# 07_-_Current_Sense.net
KiCad netlist of a schematic drawn in Altium Designer
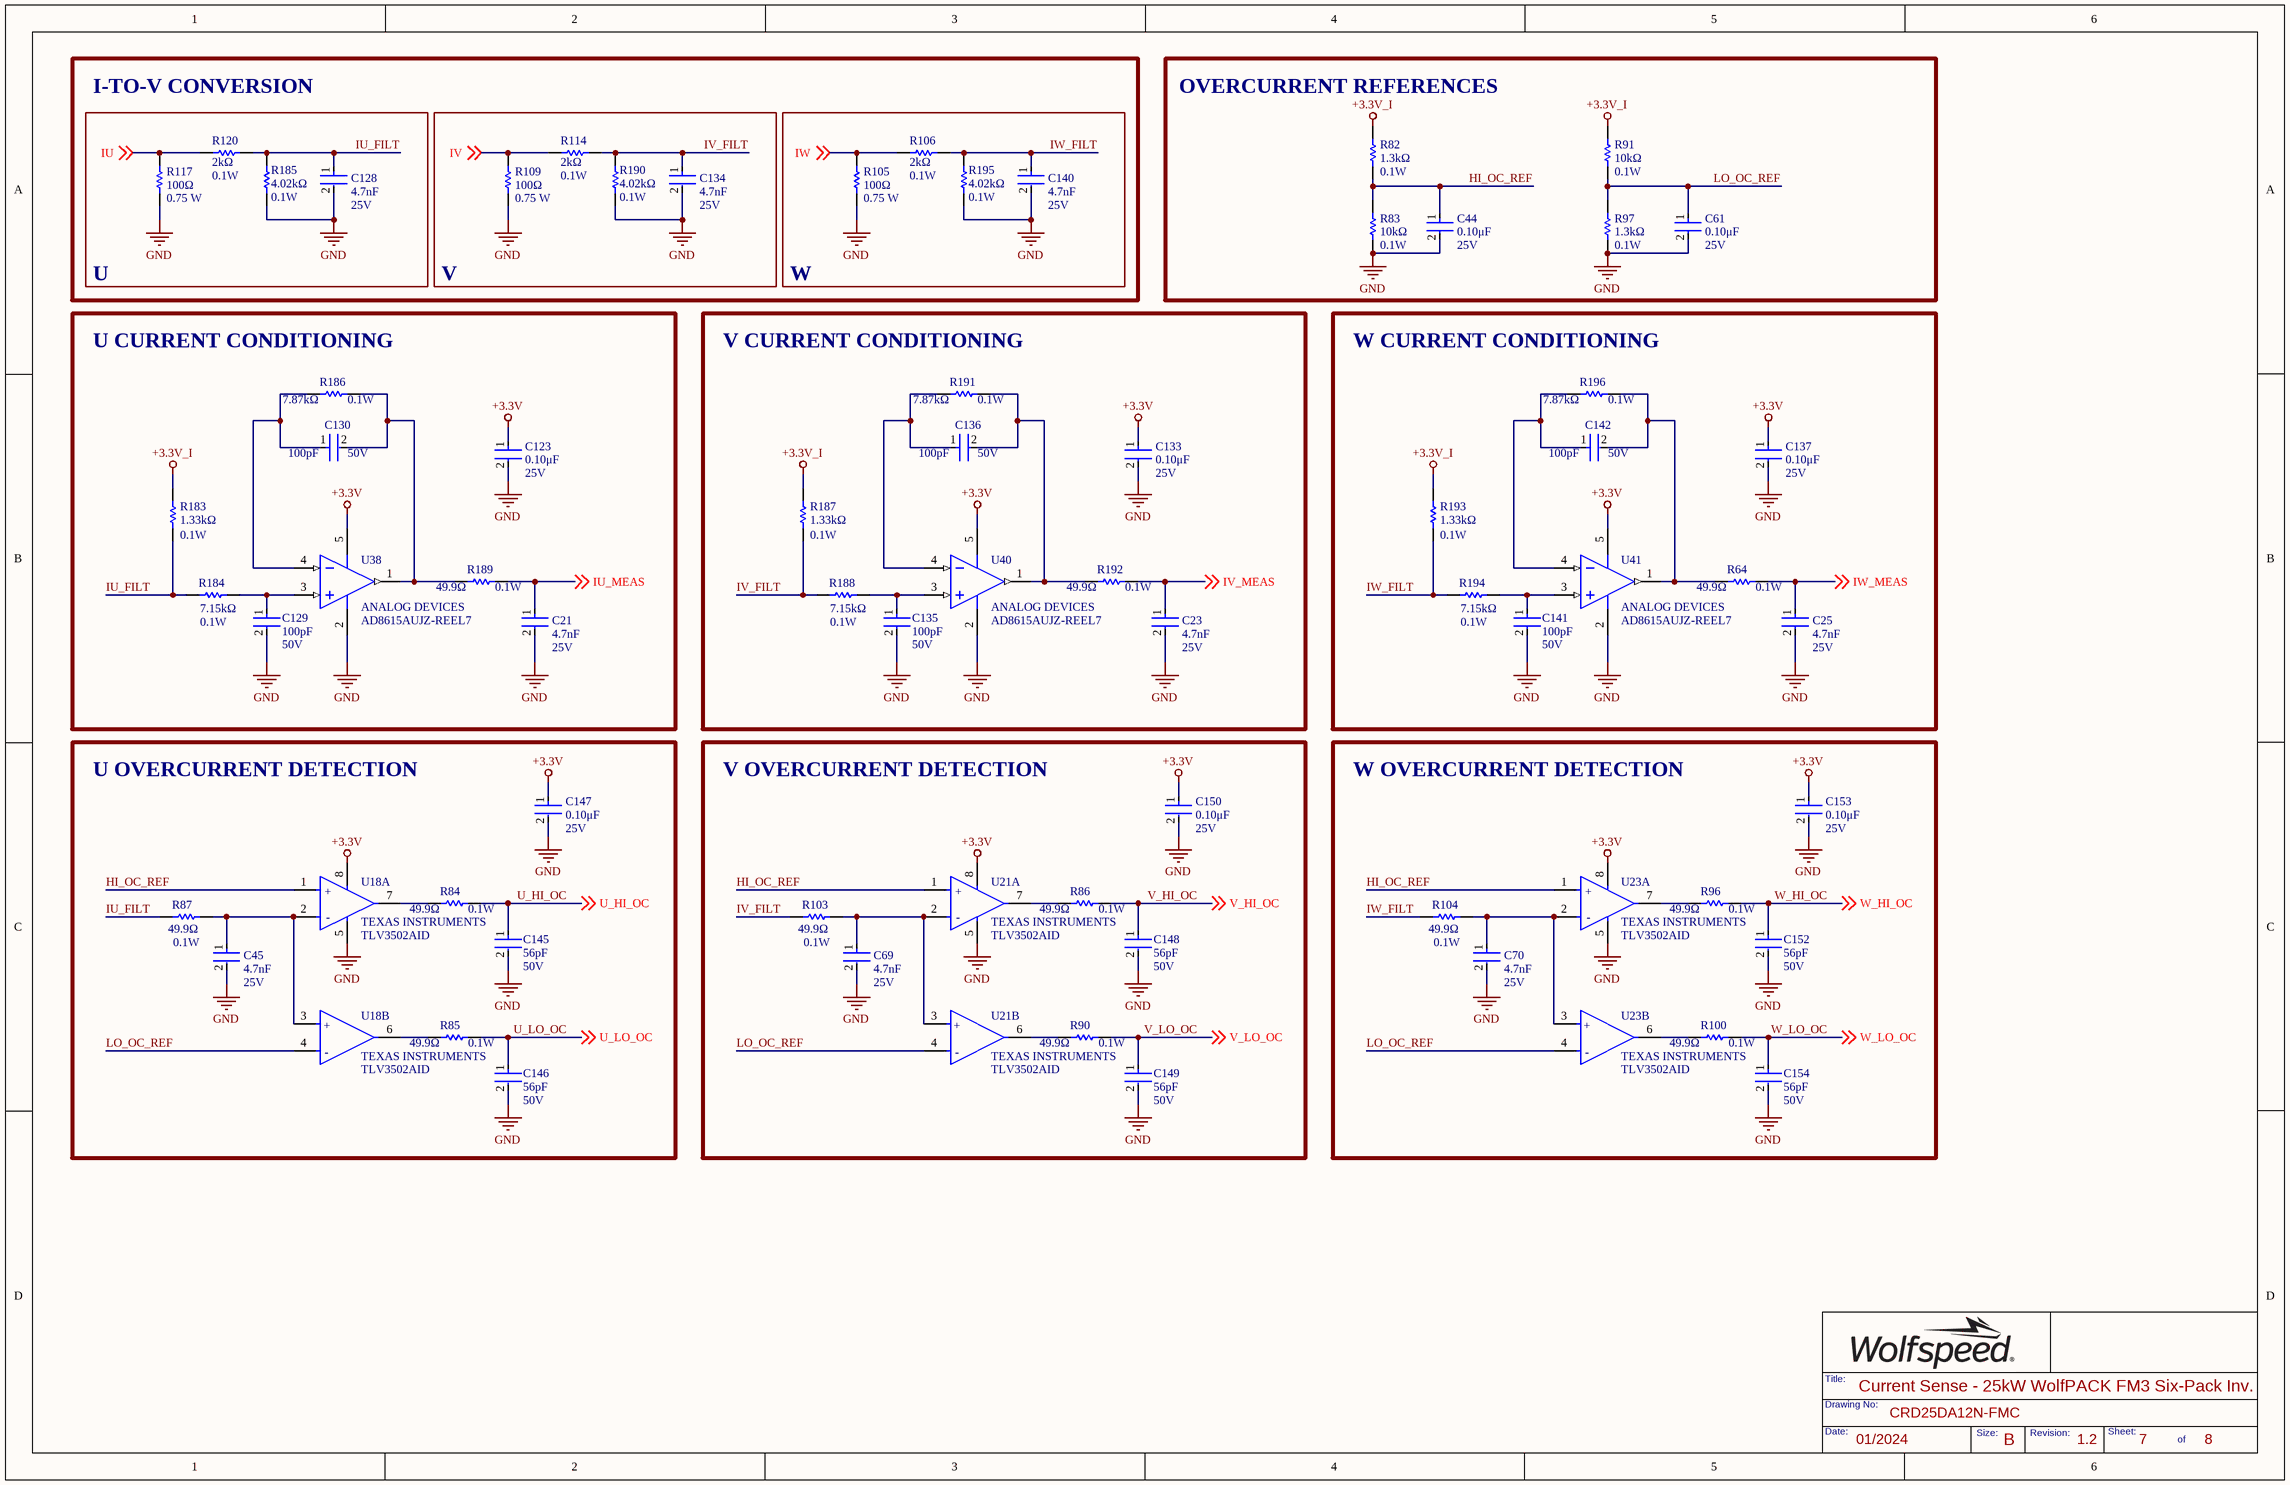
[diagram p0: 07 - Current Sense.SchDoc]

(export (version "E")
  (design (tool "Eeschema 10.0.6"))
  (components
    (comp (ref "C21")
      (value "C0603C472K3RAC7867")
      (footprint "FP-C0603C-CF-IPC_B")
      (description "CAP CER 4700PF 25V 10% X7R 0603")
      (fields
        (field (name "MANUFACTURER") "KEMET")
        (field (name "MANUFACTURER PART NUMBER") "C0603C472K3RACTU")
        (field (name "VOLTAGE RATING") "25V")
        (field (name "CAPACITANCE") "4.7nF")
      )
      (libsource (lib "Inverter_25kW") (part "C0603C472K3RAC7867"))
    )
    (comp (ref "C23")
      (value "C0603C472K3RAC7867")
      (footprint "FP-C0603C-CF-IPC_B")
      (description "CAP CER 4700PF 25V 10% X7R 0603")
      (fields
        (field (name "MANUFACTURER") "KEMET")
        (field (name "MANUFACTURER PART NUMBER") "C0603C472K3RACTU")
        (field (name "VOLTAGE RATING") "25V")
        (field (name "CAPACITANCE") "4.7nF")
      )
      (libsource (lib "Inverter_25kW") (part "C0603C472K3RAC7867"))
    )
    (comp (ref "C25")
      (value "C0603C472K3RAC7867")
      (footprint "FP-C0603C-CF-IPC_B")
      (description "CAP CER 4700PF 25V 10% X7R 0603")
      (fields
        (field (name "MANUFACTURER") "KEMET")
        (field (name "MANUFACTURER PART NUMBER") "C0603C472K3RACTU")
        (field (name "VOLTAGE RATING") "25V")
        (field (name "CAPACITANCE") "4.7nF")
      )
      (libsource (lib "Inverter_25kW") (part "C0603C472K3RAC7867"))
    )
    (comp (ref "C44")
      (value "C0603C104K3RACTU")
      (footprint "FP-C0603C-CF-IPC_B")
      (description "CAP CER 0.1UF 25V X7R 0603")
      (fields
        (field (name "VOLTAGE RATING") "25V")
        (field (name "OCTOPART") "https://octopart.com/c0603c104k3ractu-kemet-127541")
        (field (name "MANUFACTURER") "KEMET")
        (field (name "CAPACITANCE") "0.10μF")
      )
      (libsource (lib "Altium Content Vault") (part "b4654b650e69147ec39a6b967a45e02"))
    )
    (comp (ref "C45")
      (value "C0603C472K3RAC7867")
      (footprint "FP-C0603C-CF-IPC_B")
      (description "CAP CER 4700PF 25V 10% X7R 0603")
      (fields
        (field (name "MANUFACTURER") "KEMET")
        (field (name "MANUFACTURER PART NUMBER") "C0603C472K3RACTU")
        (field (name "VOLTAGE RATING") "25V")
        (field (name "CAPACITANCE") "4.7nF")
      )
      (libsource (lib "Inverter_25kW") (part "C0603C472K3RAC7867"))
    )
    (comp (ref "C61")
      (value "C0603C104K3RACTU")
      (footprint "FP-C0603C-CF-IPC_B")
      (description "CAP CER 0.1UF 25V X7R 0603")
      (fields
        (field (name "VOLTAGE RATING") "25V")
        (field (name "OCTOPART") "https://octopart.com/c0603c104k3ractu-kemet-127541")
        (field (name "MANUFACTURER") "KEMET")
        (field (name "CAPACITANCE") "0.10μF")
      )
      (libsource (lib "Altium Content Vault") (part "b4654b650e69147ec39a6b967a45e02"))
    )
    (comp (ref "C69")
      (value "C0603C472K3RAC7867")
      (footprint "FP-C0603C-CF-IPC_B")
      (description "CAP CER 4700PF 25V 10% X7R 0603")
      (fields
        (field (name "MANUFACTURER") "KEMET")
        (field (name "MANUFACTURER PART NUMBER") "C0603C472K3RACTU")
        (field (name "VOLTAGE RATING") "25V")
        (field (name "CAPACITANCE") "4.7nF")
      )
      (libsource (lib "Inverter_25kW") (part "C0603C472K3RAC7867"))
    )
    (comp (ref "C70")
      (value "C0603C472K3RAC7867")
      (footprint "FP-C0603C-CF-IPC_B")
      (description "CAP CER 4700PF 25V 10% X7R 0603")
      (fields
        (field (name "MANUFACTURER") "KEMET")
        (field (name "MANUFACTURER PART NUMBER") "C0603C472K3RACTU")
        (field (name "VOLTAGE RATING") "25V")
        (field (name "CAPACITANCE") "4.7nF")
      )
      (libsource (lib "Inverter_25kW") (part "C0603C472K3RAC7867"))
    )
    (comp (ref "C123")
      (value "C0603C104K3RACTU")
      (footprint "FP-C0603C-CF-IPC_B")
      (description "CAP CER 0.1UF 25V X7R 0603")
      (fields
        (field (name "VOLTAGE RATING") "25V")
        (field (name "OCTOPART") "https://octopart.com/c0603c104k3ractu-kemet-127541")
        (field (name "MANUFACTURER") "KEMET")
        (field (name "CAPACITANCE") "0.10μF")
      )
      (libsource (lib "Altium Content Vault") (part "b4654b650e69147ec39a6b967a45e02"))
    )
    (comp (ref "C128")
      (value "C0603C472K3RAC7867")
      (footprint "FP-C0603C-CF-IPC_B")
      (description "CAP CER 4700PF 25V 10% X7R 0603")
      (fields
        (field (name "MANUFACTURER") "KEMET")
        (field (name "MANUFACTURER PART NUMBER") "C0603C472K3RACTU")
        (field (name "VOLTAGE RATING") "25V")
        (field (name "CAPACITANCE") "4.7nF")
      )
      (libsource (lib "Inverter_25kW") (part "C0603C472K3RAC7867"))
    )
    (comp (ref "C129")
      (value "CL10C101JB8NNNC")
      (footprint "FP-C0603C-CF-IPC_B")
      (description "CAP CER 100PF 50V C0G/NP0 0603")
      (fields
        (field (name "MANUFACTURER") "SAMSUNG")
        (field (name "TOLERANCE") "5%")
        (field (name "CAPACITANCE") "100pF")
        (field (name "VOLTAGE") "50V")
      )
      (libsource (lib "Inverter_25kW") (part "CL10C101JB8NNNC"))
    )
    (comp (ref "C130")
      (value "CL10C101JB8NNNC")
      (footprint "FP-C0603C-CF-IPC_B")
      (description "CAP CER 100PF 50V C0G/NP0 0603")
      (fields
        (field (name "MANUFACTURER") "SAMSUNG")
        (field (name "TOLERANCE") "5%")
        (field (name "CAPACITANCE") "100pF")
        (field (name "VOLTAGE") "50V")
      )
      (libsource (lib "Inverter_25kW") (part "CL10C101JB8NNNC"))
    )
    (comp (ref "C133")
      (value "C0603C104K3RACTU")
      (footprint "FP-C0603C-CF-IPC_B")
      (description "CAP CER 0.1UF 25V X7R 0603")
      (fields
        (field (name "VOLTAGE RATING") "25V")
        (field (name "OCTOPART") "https://octopart.com/c0603c104k3ractu-kemet-127541")
        (field (name "MANUFACTURER") "KEMET")
        (field (name "CAPACITANCE") "0.10μF")
      )
      (libsource (lib "Altium Content Vault") (part "b4654b650e69147ec39a6b967a45e02"))
    )
    (comp (ref "C134")
      (value "C0603C472K3RAC7867")
      (footprint "FP-C0603C-CF-IPC_B")
      (description "CAP CER 4700PF 25V 10% X7R 0603")
      (fields
        (field (name "MANUFACTURER") "KEMET")
        (field (name "MANUFACTURER PART NUMBER") "C0603C472K3RACTU")
        (field (name "VOLTAGE RATING") "25V")
        (field (name "CAPACITANCE") "4.7nF")
      )
      (libsource (lib "Inverter_25kW") (part "C0603C472K3RAC7867"))
    )
    (comp (ref "C135")
      (value "CL10C101JB8NNNC")
      (footprint "FP-C0603C-CF-IPC_B")
      (description "CAP CER 100PF 50V C0G/NP0 0603")
      (fields
        (field (name "MANUFACTURER") "SAMSUNG")
        (field (name "TOLERANCE") "5%")
        (field (name "CAPACITANCE") "100pF")
        (field (name "VOLTAGE") "50V")
      )
      (libsource (lib "Inverter_25kW") (part "CL10C101JB8NNNC"))
    )
    (comp (ref "C136")
      (value "CL10C101JB8NNNC")
      (footprint "FP-C0603C-CF-IPC_B")
      (description "CAP CER 100PF 50V C0G/NP0 0603")
      (fields
        (field (name "MANUFACTURER") "SAMSUNG")
        (field (name "TOLERANCE") "5%")
        (field (name "CAPACITANCE") "100pF")
        (field (name "VOLTAGE") "50V")
      )
      (libsource (lib "Inverter_25kW") (part "CL10C101JB8NNNC"))
    )
    (comp (ref "C137")
      (value "C0603C104K3RACTU")
      (footprint "FP-C0603C-CF-IPC_B")
      (description "CAP CER 0.1UF 25V X7R 0603")
      (fields
        (field (name "VOLTAGE RATING") "25V")
        (field (name "OCTOPART") "https://octopart.com/c0603c104k3ractu-kemet-127541")
        (field (name "MANUFACTURER") "KEMET")
        (field (name "CAPACITANCE") "0.10μF")
      )
      (libsource (lib "Altium Content Vault") (part "b4654b650e69147ec39a6b967a45e02"))
    )
    (comp (ref "C140")
      (value "C0603C472K3RAC7867")
      (footprint "FP-C0603C-CF-IPC_B")
      (description "CAP CER 4700PF 25V 10% X7R 0603")
      (fields
        (field (name "MANUFACTURER") "KEMET")
        (field (name "MANUFACTURER PART NUMBER") "C0603C472K3RACTU")
        (field (name "VOLTAGE RATING") "25V")
        (field (name "CAPACITANCE") "4.7nF")
      )
      (libsource (lib "Inverter_25kW") (part "C0603C472K3RAC7867"))
    )
    (comp (ref "C141")
      (value "CL10C101JB8NNNC")
      (footprint "FP-C0603C-CF-IPC_B")
      (description "CAP CER 100PF 50V C0G/NP0 0603")
      (fields
        (field (name "MANUFACTURER") "SAMSUNG")
        (field (name "TOLERANCE") "5%")
        (field (name "CAPACITANCE") "100pF")
        (field (name "VOLTAGE") "50V")
      )
      (libsource (lib "Inverter_25kW") (part "CL10C101JB8NNNC"))
    )
    (comp (ref "C142")
      (value "CL10C101JB8NNNC")
      (footprint "FP-C0603C-CF-IPC_B")
      (description "CAP CER 100PF 50V C0G/NP0 0603")
      (fields
        (field (name "MANUFACTURER") "SAMSUNG")
        (field (name "TOLERANCE") "5%")
        (field (name "CAPACITANCE") "100pF")
        (field (name "VOLTAGE") "50V")
      )
      (libsource (lib "Inverter_25kW") (part "CL10C101JB8NNNC"))
    )
    (comp (ref "C145")
      (value "CL10C560JB8NNNC")
      (footprint "FP-C0603C-CF-IPC_B")
      (description "CAP CER 56PF 50V C0G/NP0 0603")
      (fields
        (field (name "MANUFACTURER") "SAMSUNG")
        (field (name "TOLERANCE") "5%")
        (field (name "CAPACITANCE") "56pF")
        (field (name "VOLTAGE RATING") "50V")
      )
      (libsource (lib "Inverter_25kW") (part "CL10C560JB8NNNC"))
    )
    (comp (ref "C146")
      (value "CL10C560JB8NNNC")
      (footprint "FP-C0603C-CF-IPC_B")
      (description "CAP CER 56PF 50V C0G/NP0 0603")
      (fields
        (field (name "MANUFACTURER") "SAMSUNG")
        (field (name "TOLERANCE") "5%")
        (field (name "CAPACITANCE") "56pF")
        (field (name "VOLTAGE RATING") "50V")
      )
      (libsource (lib "Inverter_25kW") (part "CL10C560JB8NNNC"))
    )
    (comp (ref "C147")
      (value "C0603C104K3RACTU")
      (footprint "FP-C0603C-CF-IPC_B")
      (description "CAP CER 0.1UF 25V X7R 0603")
      (fields
        (field (name "VOLTAGE RATING") "25V")
        (field (name "OCTOPART") "https://octopart.com/c0603c104k3ractu-kemet-127541")
        (field (name "MANUFACTURER") "KEMET")
        (field (name "CAPACITANCE") "0.10μF")
      )
      (libsource (lib "Altium Content Vault") (part "b4654b650e69147ec39a6b967a45e02"))
    )
    (comp (ref "C148")
      (value "CL10C560JB8NNNC")
      (footprint "FP-C0603C-CF-IPC_B")
      (description "CAP CER 56PF 50V C0G/NP0 0603")
      (fields
        (field (name "MANUFACTURER") "SAMSUNG")
        (field (name "TOLERANCE") "5%")
        (field (name "CAPACITANCE") "56pF")
        (field (name "VOLTAGE RATING") "50V")
      )
      (libsource (lib "Inverter_25kW") (part "CL10C560JB8NNNC"))
    )
    (comp (ref "C149")
      (value "CL10C560JB8NNNC")
      (footprint "FP-C0603C-CF-IPC_B")
      (description "CAP CER 56PF 50V C0G/NP0 0603")
      (fields
        (field (name "MANUFACTURER") "SAMSUNG")
        (field (name "TOLERANCE") "5%")
        (field (name "CAPACITANCE") "56pF")
        (field (name "VOLTAGE RATING") "50V")
      )
      (libsource (lib "Inverter_25kW") (part "CL10C560JB8NNNC"))
    )
    (comp (ref "C150")
      (value "C0603C104K3RACTU")
      (footprint "FP-C0603C-CF-IPC_B")
      (description "CAP CER 0.1UF 25V X7R 0603")
      (fields
        (field (name "VOLTAGE RATING") "25V")
        (field (name "OCTOPART") "https://octopart.com/c0603c104k3ractu-kemet-127541")
        (field (name "MANUFACTURER") "KEMET")
        (field (name "CAPACITANCE") "0.10μF")
      )
      (libsource (lib "Altium Content Vault") (part "b4654b650e69147ec39a6b967a45e02"))
    )
    (comp (ref "C152")
      (value "CL10C560JB8NNNC")
      (footprint "FP-C0603C-CF-IPC_B")
      (description "CAP CER 56PF 50V C0G/NP0 0603")
      (fields
        (field (name "MANUFACTURER") "SAMSUNG")
        (field (name "TOLERANCE") "5%")
        (field (name "CAPACITANCE") "56pF")
        (field (name "VOLTAGE RATING") "50V")
      )
      (libsource (lib "Inverter_25kW") (part "CL10C560JB8NNNC"))
    )
    (comp (ref "C153")
      (value "C0603C104K3RACTU")
      (footprint "FP-C0603C-CF-IPC_B")
      (description "CAP CER 0.1UF 25V X7R 0603")
      (fields
        (field (name "VOLTAGE RATING") "25V")
        (field (name "OCTOPART") "https://octopart.com/c0603c104k3ractu-kemet-127541")
        (field (name "MANUFACTURER") "KEMET")
        (field (name "CAPACITANCE") "0.10μF")
      )
      (libsource (lib "Altium Content Vault") (part "b4654b650e69147ec39a6b967a45e02"))
    )
    (comp (ref "C154")
      (value "CL10C560JB8NNNC")
      (footprint "FP-C0603C-CF-IPC_B")
      (description "CAP CER 56PF 50V C0G/NP0 0603")
      (fields
        (field (name "MANUFACTURER") "SAMSUNG")
        (field (name "TOLERANCE") "5%")
        (field (name "CAPACITANCE") "56pF")
        (field (name "VOLTAGE RATING") "50V")
      )
      (libsource (lib "Inverter_25kW") (part "CL10C560JB8NNNC"))
    )
    (comp (ref "R64")
      (value "ERJ-3EKF49R9V")
      (footprint "FP-MCR03-IPC_B")
      (description "RES SMD 49.9 OHM 1% 1/10W 0603")
      (fields
        (field (name "MANUFACTURER") "PANASONIC")
        (field (name "TOLERANCE") "1%")
        (field (name "RESISTANCE") "49.9Ω")
        (field (name "POWER RATING") "0.1W")
      )
      (libsource (lib "Inverter_25kW") (part "ERJ-3EKF49R9V"))
    )
    (comp (ref "R82")
      (value "ERA3AEB132V")
      (footprint "FP-MCR03-IPC_B")
      (description "RES SMD 1.3K OHM 0.1% 1/10W 0603")
      (fields
        (field (name "MANUFACTURER") "PANASONIC")
        (field (name "MANUFACTURER PART NUMBER") "ERA-3AEB132V")
        (field (name "POWER RATING") "0.1W")
        (field (name "RESISTANCE") "1.3kΩ")
      )
      (libsource (lib "Inverter_25kW") (part "ERA3AEB132V"))
    )
    (comp (ref "R83")
      (value "ERJ3EKF1002V")
      (footprint "FP-MCR03-IPC_B")
      (description "RES SMD 10K OHM 1% 1/10W 0603")
      (fields
        (field (name "MANUFACTURER") "PANASONIC")
        (field (name "MANUFACTURER PART NUMBER") "ERJ-3EKF1002V")
        (field (name "RESISTANCE") "10kΩ")
        (field (name "MAX POWER DISSIPATION") "0.1W")
      )
      (libsource (lib "Inverter_25kW") (part "ERJ3EKF1002V"))
    )
    (comp (ref "R84")
      (value "ERJ-3EKF49R9V")
      (footprint "FP-MCR03-IPC_B")
      (description "RES SMD 49.9 OHM 1% 1/10W 0603")
      (fields
        (field (name "MANUFACTURER") "PANASONIC")
        (field (name "TOLERANCE") "1%")
        (field (name "RESISTANCE") "49.9Ω")
        (field (name "POWER RATING") "0.1W")
      )
      (libsource (lib "Inverter_25kW") (part "ERJ-3EKF49R9V"))
    )
    (comp (ref "R85")
      (value "ERJ-3EKF49R9V")
      (footprint "FP-MCR03-IPC_B")
      (description "RES SMD 49.9 OHM 1% 1/10W 0603")
      (fields
        (field (name "MANUFACTURER") "PANASONIC")
        (field (name "TOLERANCE") "1%")
        (field (name "RESISTANCE") "49.9Ω")
        (field (name "POWER RATING") "0.1W")
      )
      (libsource (lib "Inverter_25kW") (part "ERJ-3EKF49R9V"))
    )
    (comp (ref "R86")
      (value "ERJ-3EKF49R9V")
      (footprint "FP-MCR03-IPC_B")
      (description "RES SMD 49.9 OHM 1% 1/10W 0603")
      (fields
        (field (name "MANUFACTURER") "PANASONIC")
        (field (name "TOLERANCE") "1%")
        (field (name "RESISTANCE") "49.9Ω")
        (field (name "POWER RATING") "0.1W")
      )
      (libsource (lib "Inverter_25kW") (part "ERJ-3EKF49R9V"))
    )
    (comp (ref "R87")
      (value "ERJ-3EKF49R9V")
      (footprint "FP-MCR03-IPC_B")
      (description "RES SMD 49.9 OHM 1% 1/10W 0603")
      (fields
        (field (name "MANUFACTURER") "PANASONIC")
        (field (name "TOLERANCE") "1%")
        (field (name "RESISTANCE") "49.9Ω")
        (field (name "POWER RATING") "0.1W")
      )
      (libsource (lib "Inverter_25kW") (part "ERJ-3EKF49R9V"))
    )
    (comp (ref "R90")
      (value "ERJ-3EKF49R9V")
      (footprint "FP-MCR03-IPC_B")
      (description "RES SMD 49.9 OHM 1% 1/10W 0603")
      (fields
        (field (name "MANUFACTURER") "PANASONIC")
        (field (name "TOLERANCE") "1%")
        (field (name "RESISTANCE") "49.9Ω")
        (field (name "POWER RATING") "0.1W")
      )
      (libsource (lib "Inverter_25kW") (part "ERJ-3EKF49R9V"))
    )
    (comp (ref "R91")
      (value "ERJ3EKF1002V")
      (footprint "FP-MCR03-IPC_B")
      (description "RES SMD 10K OHM 1% 1/10W 0603")
      (fields
        (field (name "MANUFACTURER") "PANASONIC")
        (field (name "MANUFACTURER PART NUMBER") "ERJ-3EKF1002V")
        (field (name "RESISTANCE") "10kΩ")
        (field (name "MAX POWER DISSIPATION") "0.1W")
      )
      (libsource (lib "Inverter_25kW") (part "ERJ3EKF1002V"))
    )
    (comp (ref "R96")
      (value "ERJ-3EKF49R9V")
      (footprint "FP-MCR03-IPC_B")
      (description "RES SMD 49.9 OHM 1% 1/10W 0603")
      (fields
        (field (name "MANUFACTURER") "PANASONIC")
        (field (name "TOLERANCE") "1%")
        (field (name "RESISTANCE") "49.9Ω")
        (field (name "POWER RATING") "0.1W")
      )
      (libsource (lib "Inverter_25kW") (part "ERJ-3EKF49R9V"))
    )
    (comp (ref "R97")
      (value "ERA3AEB132V")
      (footprint "FP-MCR03-IPC_B")
      (description "RES SMD 1.3K OHM 0.1% 1/10W 0603")
      (fields
        (field (name "MANUFACTURER") "PANASONIC")
        (field (name "MANUFACTURER PART NUMBER") "ERA-3AEB132V")
        (field (name "POWER RATING") "0.1W")
        (field (name "RESISTANCE") "1.3kΩ")
      )
      (libsource (lib "Inverter_25kW") (part "ERA3AEB132V"))
    )
    (comp (ref "R100")
      (value "ERJ-3EKF49R9V")
      (footprint "FP-MCR03-IPC_B")
      (description "RES SMD 49.9 OHM 1% 1/10W 0603")
      (fields
        (field (name "MANUFACTURER") "PANASONIC")
        (field (name "TOLERANCE") "1%")
        (field (name "RESISTANCE") "49.9Ω")
        (field (name "POWER RATING") "0.1W")
      )
      (libsource (lib "Inverter_25kW") (part "ERJ-3EKF49R9V"))
    )
    (comp (ref "R103")
      (value "ERJ-3EKF49R9V")
      (footprint "FP-MCR03-IPC_B")
      (description "RES SMD 49.9 OHM 1% 1/10W 0603")
      (fields
        (field (name "MANUFACTURER") "PANASONIC")
        (field (name "TOLERANCE") "1%")
        (field (name "RESISTANCE") "49.9Ω")
        (field (name "POWER RATING") "0.1W")
      )
      (libsource (lib "Inverter_25kW") (part "ERJ-3EKF49R9V"))
    )
    (comp (ref "R104")
      (value "ERJ-3EKF49R9V")
      (footprint "FP-MCR03-IPC_B")
      (description "RES SMD 49.9 OHM 1% 1/10W 0603")
      (fields
        (field (name "MANUFACTURER") "PANASONIC")
        (field (name "TOLERANCE") "1%")
        (field (name "RESISTANCE") "49.9Ω")
        (field (name "POWER RATING") "0.1W")
      )
      (libsource (lib "Inverter_25kW") (part "ERJ-3EKF49R9V"))
    )
    (comp (ref "R105")
      (value "100Ω")
      (footprint "RESC2010(5025)_N")
      (description "RES 100 OHM 1% 3/4W 2010")
      (fields
        (field (name "TOLERANCE") "1 %")
        (field (name "POWER") "0.75 W")
        (field (name "MANUFACTURER") "YAGEO")
      )
      (libsource (lib "Altium Content Vault") (part "RES"))
    )
    (comp (ref "R106")
      (value "RT0603DRE072KL")
      (footprint "FP-MCR03-IPC_B")
      (description "RES SMD 2K OHM 0.5% 1/10W 0603")
      (fields
        (field (name "MANUFACTURER") "YAGEO")
        (field (name "TOLERANCE") "0.5%")
        (field (name "RESISTANCE") "2kΩ")
        (field (name "POWER RATING") "0.1W")
      )
      (libsource (lib "Inverter_25kW") (part "RT0603DRE072KL"))
    )
    (comp (ref "R109")
      (value "100Ω")
      (footprint "RESC2010(5025)_N")
      (description "RES 100 OHM 1% 3/4W 2010")
      (fields
        (field (name "TOLERANCE") "1 %")
        (field (name "POWER") "0.75 W")
        (field (name "MANUFACTURER") "YAGEO")
      )
      (libsource (lib "Altium Content Vault") (part "RES"))
    )
    (comp (ref "R114")
      (value "RT0603DRE072KL")
      (footprint "FP-MCR03-IPC_B")
      (description "RES SMD 2K OHM 0.5% 1/10W 0603")
      (fields
        (field (name "MANUFACTURER") "YAGEO")
        (field (name "TOLERANCE") "0.5%")
        (field (name "RESISTANCE") "2kΩ")
        (field (name "POWER RATING") "0.1W")
      )
      (libsource (lib "Inverter_25kW") (part "RT0603DRE072KL"))
    )
    (comp (ref "R117")
      (value "100Ω")
      (footprint "RESC2010(5025)_N")
      (description "RES 100 OHM 1% 3/4W 2010")
      (fields
        (field (name "TOLERANCE") "1 %")
        (field (name "POWER") "0.75 W")
        (field (name "MANUFACTURER") "YAGEO")
      )
      (libsource (lib "Altium Content Vault") (part "RES"))
    )
    (comp (ref "R120")
      (value "RT0603DRE072KL")
      (footprint "FP-MCR03-IPC_B")
      (description "RES SMD 2K OHM 0.5% 1/10W 0603")
      (fields
        (field (name "MANUFACTURER") "YAGEO")
        (field (name "TOLERANCE") "0.5%")
        (field (name "RESISTANCE") "2kΩ")
        (field (name "POWER RATING") "0.1W")
      )
      (libsource (lib "Inverter_25kW") (part "RT0603DRE072KL"))
    )
    (comp (ref "R183")
      (value "RMCF0603FT1K33")
      (footprint "FP-MCR03-IPC_B")
      (description "RES 1.33K OHM 1% 1/10W 0603")
      (fields
        (field (name "MANUFACTURER") "STACKPOLE")
        (field (name "TOLERANCE") "1%")
        (field (name "POWER RATING") "0.1W")
        (field (name "RESISTANCE") "1.33kΩ")
      )
      (libsource (lib "Inverter_25kW") (part "RMCF0603FT1K33"))
    )
    (comp (ref "R184")
      (value "RMCF0603FT7K15")
      (footprint "FP-MCR03-IPC_B")
      (description "RES 7.15K OHM 1% 1/10W 0603")
      (fields
        (field (name "MANUFACTURER") "STACKPOLE")
        (field (name "TOLERANCE") "1%")
        (field (name "RESISTANCE") "7.15kΩ")
        (field (name "POWER RATING") "0.1W")
      )
      (libsource (lib "Inverter_25kW") (part "RMCF0603FT7K15"))
    )
    (comp (ref "R185")
      (value "ERA3AEB4021V")
      (footprint "FP-MCR03-IPC_B")
      (description "RES SMD 4.02KOHM 0.1% 1/10W 0603")
      (fields
        (field (name "MANUFACTURER") "PANASONIC")
        (field (name "MANUFACTURER PART NUMBER") "ERA-3AEB4021V")
        (field (name "RESISTANCE") "4.02kΩ")
        (field (name "POWER RATING") "0.1W")
      )
      (libsource (lib "Inverter_25kW") (part "ERA3AEB4021V"))
    )
    (comp (ref "R186")
      (value "RC0603FR-077K87L")
      (footprint "FP-MCR03-IPC_B")
      (description "RES 7.87K OHM 1% 1/10W 0603")
      (fields
        (field (name "MANUFACTURER") "YAGEO")
        (field (name "TOLERANCE") "1%")
        (field (name "RESISTANCE") "7.87kΩ")
        (field (name "MAX POWER DISSIPATION") "0.1W")
      )
      (libsource (lib "Inverter_25kW") (part "RC0603FR-077K87L"))
    )
    (comp (ref "R187")
      (value "RMCF0603FT1K33")
      (footprint "FP-MCR03-IPC_B")
      (description "RES 1.33K OHM 1% 1/10W 0603")
      (fields
        (field (name "MANUFACTURER") "STACKPOLE")
        (field (name "TOLERANCE") "1%")
        (field (name "POWER RATING") "0.1W")
        (field (name "RESISTANCE") "1.33kΩ")
      )
      (libsource (lib "Inverter_25kW") (part "RMCF0603FT1K33"))
    )
    (comp (ref "R188")
      (value "RMCF0603FT7K15")
      (footprint "FP-MCR03-IPC_B")
      (description "RES 7.15K OHM 1% 1/10W 0603")
      (fields
        (field (name "MANUFACTURER") "STACKPOLE")
        (field (name "TOLERANCE") "1%")
        (field (name "RESISTANCE") "7.15kΩ")
        (field (name "POWER RATING") "0.1W")
      )
      (libsource (lib "Inverter_25kW") (part "RMCF0603FT7K15"))
    )
    (comp (ref "R189")
      (value "ERJ-3EKF49R9V")
      (footprint "FP-MCR03-IPC_B")
      (description "RES SMD 49.9 OHM 1% 1/10W 0603")
      (fields
        (field (name "MANUFACTURER") "PANASONIC")
        (field (name "TOLERANCE") "1%")
        (field (name "RESISTANCE") "49.9Ω")
        (field (name "POWER RATING") "0.1W")
      )
      (libsource (lib "Inverter_25kW") (part "ERJ-3EKF49R9V"))
    )
    (comp (ref "R190")
      (value "ERA3AEB4021V")
      (footprint "FP-MCR03-IPC_B")
      (description "RES SMD 4.02KOHM 0.1% 1/10W 0603")
      (fields
        (field (name "MANUFACTURER") "PANASONIC")
        (field (name "MANUFACTURER PART NUMBER") "ERA-3AEB4021V")
        (field (name "RESISTANCE") "4.02kΩ")
        (field (name "POWER RATING") "0.1W")
      )
      (libsource (lib "Inverter_25kW") (part "ERA3AEB4021V"))
    )
    (comp (ref "R191")
      (value "RC0603FR-077K87L")
      (footprint "FP-MCR03-IPC_B")
      (description "RES 7.87K OHM 1% 1/10W 0603")
      (fields
        (field (name "MANUFACTURER") "YAGEO")
        (field (name "TOLERANCE") "1%")
        (field (name "RESISTANCE") "7.87kΩ")
        (field (name "MAX POWER DISSIPATION") "0.1W")
      )
      (libsource (lib "Inverter_25kW") (part "RC0603FR-077K87L"))
    )
    (comp (ref "R192")
      (value "ERJ-3EKF49R9V")
      (footprint "FP-MCR03-IPC_B")
      (description "RES SMD 49.9 OHM 1% 1/10W 0603")
      (fields
        (field (name "MANUFACTURER") "PANASONIC")
        (field (name "TOLERANCE") "1%")
        (field (name "RESISTANCE") "49.9Ω")
        (field (name "POWER RATING") "0.1W")
      )
      (libsource (lib "Inverter_25kW") (part "ERJ-3EKF49R9V"))
    )
    (comp (ref "R193")
      (value "RMCF0603FT1K33")
      (footprint "FP-MCR03-IPC_B")
      (description "RES 1.33K OHM 1% 1/10W 0603")
      (fields
        (field (name "MANUFACTURER") "STACKPOLE")
        (field (name "TOLERANCE") "1%")
        (field (name "POWER RATING") "0.1W")
        (field (name "RESISTANCE") "1.33kΩ")
      )
      (libsource (lib "Inverter_25kW") (part "RMCF0603FT1K33"))
    )
    (comp (ref "R194")
      (value "RMCF0603FT7K15")
      (footprint "FP-MCR03-IPC_B")
      (description "RES 7.15K OHM 1% 1/10W 0603")
      (fields
        (field (name "MANUFACTURER") "STACKPOLE")
        (field (name "TOLERANCE") "1%")
        (field (name "RESISTANCE") "7.15kΩ")
        (field (name "POWER RATING") "0.1W")
      )
      (libsource (lib "Inverter_25kW") (part "RMCF0603FT7K15"))
    )
    (comp (ref "R195")
      (value "ERA3AEB4021V")
      (footprint "FP-MCR03-IPC_B")
      (description "RES SMD 4.02KOHM 0.1% 1/10W 0603")
      (fields
        (field (name "MANUFACTURER") "PANASONIC")
        (field (name "MANUFACTURER PART NUMBER") "ERA-3AEB4021V")
        (field (name "RESISTANCE") "4.02kΩ")
        (field (name "POWER RATING") "0.1W")
      )
      (libsource (lib "Inverter_25kW") (part "ERA3AEB4021V"))
    )
    (comp (ref "R196")
      (value "RC0603FR-077K87L")
      (footprint "FP-MCR03-IPC_B")
      (description "RES 7.87K OHM 1% 1/10W 0603")
      (fields
        (field (name "MANUFACTURER") "YAGEO")
        (field (name "TOLERANCE") "1%")
        (field (name "RESISTANCE") "7.87kΩ")
        (field (name "MAX POWER DISSIPATION") "0.1W")
      )
      (libsource (lib "Inverter_25kW") (part "RC0603FR-077K87L"))
    )
    (comp (ref "U18")
      (value "TLV3502AID")
      (footprint "FP-D0008A-IPC_B")
      (description "IC COMPARATOR R-R HI-SPD 8-SOIC")
      (fields
        (field (name "OCTOPART") "https://octopart.com/tlv3502aid-texas+instruments-428400")
        (field (name "MANUFACTURER") "TEXAS INSTRUMENTS")
        (field (name "MANUFACTURER PRINT") "TEXAS INSTRUMENTS")
      )
      (libsource (lib "Inverter_25kW") (part "CMP-04896-000023-1"))
    )
    (comp (ref "U21")
      (value "TLV3502AID")
      (footprint "FP-D0008A-IPC_B")
      (description "IC COMPARATOR R-R HI-SPD 8-SOIC")
      (fields
        (field (name "OCTOPART") "https://octopart.com/tlv3502aid-texas+instruments-428400")
        (field (name "MANUFACTURER") "TEXAS INSTRUMENTS")
        (field (name "MANUFACTURER PRINT") "TEXAS INSTRUMENTS")
      )
      (libsource (lib "Inverter_25kW") (part "CMP-04896-000023-1"))
    )
    (comp (ref "U23")
      (value "TLV3502AID")
      (footprint "FP-D0008A-IPC_B")
      (description "IC COMPARATOR R-R HI-SPD 8-SOIC")
      (fields
        (field (name "OCTOPART") "https://octopart.com/tlv3502aid-texas+instruments-428400")
        (field (name "MANUFACTURER") "TEXAS INSTRUMENTS")
        (field (name "MANUFACTURER PRINT") "TEXAS INSTRUMENTS")
      )
      (libsource (lib "Inverter_25kW") (part "CMP-04896-000023-1"))
    )
    (comp (ref "U38")
      (value "AD8615AUJZ-REEL7")
      (footprint "ADI-UJ-5_M")
      (description "IC OPAMP GP 1 CIRCUIT TSOT23-5")
      (fields
        (field (name "MANUFACTURER") "ANALOG DEVICES")
        (field (name "GENERIC PART NUMBER") "AD8615")
        (field (name "MANUFACTURER PART NUMBER") "AD8615AUJZ-REEL7")
      )
      (libsource (lib "Altium Content Vault") (part "ADI-ADxxxx-X-5"))
    )
    (comp (ref "U40")
      (value "AD8615AUJZ-REEL7")
      (footprint "ADI-UJ-5_M")
      (description "IC OPAMP GP 1 CIRCUIT TSOT23-5")
      (fields
        (field (name "MANUFACTURER") "ANALOG DEVICES")
        (field (name "GENERIC PART NUMBER") "AD8615")
        (field (name "MANUFACTURER PART NUMBER") "AD8615AUJZ-REEL7")
      )
      (libsource (lib "Altium Content Vault") (part "ADI-ADxxxx-X-5"))
    )
    (comp (ref "U41")
      (value "AD8615AUJZ-REEL7")
      (footprint "ADI-UJ-5_M")
      (description "IC OPAMP GP 1 CIRCUIT TSOT23-5")
      (fields
        (field (name "MANUFACTURER") "ANALOG DEVICES")
        (field (name "GENERIC PART NUMBER") "AD8615")
        (field (name "MANUFACTURER PART NUMBER") "AD8615AUJZ-REEL7")
      )
      (libsource (lib "Altium Content Vault") (part "ADI-ADxxxx-X-5"))
    )
  )
  (nets
    (net (code "1") (name "+3.3V") (class "Default")
      (node (ref "C123") (pin "1") (pinfunction "1_1") (pintype "passive"))
      (node (ref "C133") (pin "1") (pinfunction "1_1") (pintype "passive"))
      (node (ref "C137") (pin "1") (pinfunction "1_1") (pintype "passive"))
      (node (ref "C147") (pin "1") (pinfunction "1_1") (pintype "passive"))
      (node (ref "C150") (pin "1") (pinfunction "1_1") (pintype "passive"))
      (node (ref "C153") (pin "1") (pinfunction "1_1") (pintype "passive"))
      (node (ref "U18") (pin "8") (pinfunction "V+_8") (pintype "power_in"))
      (node (ref "U21") (pin "8") (pinfunction "V+_8") (pintype "power_in"))
      (node (ref "U23") (pin "8") (pinfunction "V+_8") (pintype "power_in"))
      (node (ref "U38") (pin "5") (pinfunction "+V_5") (pintype "power_in"))
      (node (ref "U40") (pin "5") (pinfunction "+V_5") (pintype "power_in"))
      (node (ref "U41") (pin "5") (pinfunction "+V_5") (pintype "power_in"))
    )
    (net (code "2") (name "+3.3V_I") (class "Default")
      (node (ref "R183") (pin "2") (pinfunction "2_2") (pintype "passive"))
      (node (ref "R187") (pin "2") (pinfunction "2_2") (pintype "passive"))
      (node (ref "R193") (pin "2") (pinfunction "2_2") (pintype "passive"))
      (node (ref "R82") (pin "2") (pinfunction "2_2") (pintype "passive"))
      (node (ref "R91") (pin "2") (pinfunction "2_2") (pintype "passive"))
    )
    (net (code "3") (name "/HI_OC_REF") (class "Default")
      (node (ref "C44") (pin "1") (pinfunction "1_1") (pintype "passive"))
      (node (ref "R82") (pin "1") (pinfunction "1_1") (pintype "passive"))
      (node (ref "R83") (pin "2") (pinfunction "2_2") (pintype "passive"))
      (node (ref "U18") (pin "1") (pinfunction "+IN_A_1") (pintype "tri_state"))
      (node (ref "U21") (pin "1") (pinfunction "+IN_A_1") (pintype "tri_state"))
      (node (ref "U23") (pin "1") (pinfunction "+IN_A_1") (pintype "tri_state"))
    )
    (net (code "4") (name "/IU_FILT") (class "Default")
      (node (ref "C128") (pin "1") (pinfunction "1_1") (pintype "passive"))
      (node (ref "R120") (pin "2") (pinfunction "2_2") (pintype "passive"))
      (node (ref "R183") (pin "1") (pinfunction "1_1") (pintype "passive"))
      (node (ref "R184") (pin "1") (pinfunction "1_1") (pintype "passive"))
      (node (ref "R185") (pin "2") (pinfunction "2_2") (pintype "passive"))
      (node (ref "R87") (pin "1") (pinfunction "1_1") (pintype "passive"))
    )
    (net (code "5") (name "/IV_FILT") (class "Default")
      (node (ref "C134") (pin "1") (pinfunction "1_1") (pintype "passive"))
      (node (ref "R103") (pin "1") (pinfunction "1_1") (pintype "passive"))
      (node (ref "R114") (pin "2") (pinfunction "2_2") (pintype "passive"))
      (node (ref "R187") (pin "1") (pinfunction "1_1") (pintype "passive"))
      (node (ref "R188") (pin "1") (pinfunction "1_1") (pintype "passive"))
      (node (ref "R190") (pin "2") (pinfunction "2_2") (pintype "passive"))
    )
    (net (code "6") (name "/IW_FILT") (class "Default")
      (node (ref "C140") (pin "1") (pinfunction "1_1") (pintype "passive"))
      (node (ref "R104") (pin "1") (pinfunction "1_1") (pintype "passive"))
      (node (ref "R106") (pin "2") (pinfunction "2_2") (pintype "passive"))
      (node (ref "R193") (pin "1") (pinfunction "1_1") (pintype "passive"))
      (node (ref "R194") (pin "1") (pinfunction "1_1") (pintype "passive"))
      (node (ref "R195") (pin "2") (pinfunction "2_2") (pintype "passive"))
    )
    (net (code "7") (name "/LO_OC_REF") (class "Default")
      (node (ref "C61") (pin "1") (pinfunction "1_1") (pintype "passive"))
      (node (ref "R91") (pin "1") (pinfunction "1_1") (pintype "passive"))
      (node (ref "R97") (pin "2") (pinfunction "2_2") (pintype "passive"))
      (node (ref "U18") (pin "4") (pinfunction "-IN_B_4") (pintype "tri_state"))
      (node (ref "U21") (pin "4") (pinfunction "-IN_B_4") (pintype "tri_state"))
      (node (ref "U23") (pin "4") (pinfunction "-IN_B_4") (pintype "tri_state"))
    )
    (net (code "8") (name "GND") (class "Default")
      (node (ref "C123") (pin "2") (pinfunction "2_2") (pintype "passive"))
      (node (ref "C128") (pin "2") (pinfunction "2_2") (pintype "passive"))
      (node (ref "C129") (pin "2") (pinfunction "2_2") (pintype "passive"))
      (node (ref "C133") (pin "2") (pinfunction "2_2") (pintype "passive"))
      (node (ref "C134") (pin "2") (pinfunction "2_2") (pintype "passive"))
      (node (ref "C135") (pin "2") (pinfunction "2_2") (pintype "passive"))
      (node (ref "C137") (pin "2") (pinfunction "2_2") (pintype "passive"))
      (node (ref "C140") (pin "2") (pinfunction "2_2") (pintype "passive"))
      (node (ref "C141") (pin "2") (pinfunction "2_2") (pintype "passive"))
      (node (ref "C145") (pin "2") (pinfunction "2_2") (pintype "passive"))
      (node (ref "C146") (pin "2") (pinfunction "2_2") (pintype "passive"))
      (node (ref "C147") (pin "2") (pinfunction "2_2") (pintype "passive"))
      (node (ref "C148") (pin "2") (pinfunction "2_2") (pintype "passive"))
      (node (ref "C149") (pin "2") (pinfunction "2_2") (pintype "passive"))
      (node (ref "C150") (pin "2") (pinfunction "2_2") (pintype "passive"))
      (node (ref "C152") (pin "2") (pinfunction "2_2") (pintype "passive"))
      (node (ref "C153") (pin "2") (pinfunction "2_2") (pintype "passive"))
      (node (ref "C154") (pin "2") (pinfunction "2_2") (pintype "passive"))
      (node (ref "C21") (pin "2") (pinfunction "2_2") (pintype "passive"))
      (node (ref "C23") (pin "2") (pinfunction "2_2") (pintype "passive"))
      (node (ref "C25") (pin "2") (pinfunction "2_2") (pintype "passive"))
      (node (ref "C44") (pin "2") (pinfunction "2_2") (pintype "passive"))
      (node (ref "C45") (pin "2") (pinfunction "2_2") (pintype "passive"))
      (node (ref "C61") (pin "2") (pinfunction "2_2") (pintype "passive"))
      (node (ref "C69") (pin "2") (pinfunction "2_2") (pintype "passive"))
      (node (ref "C70") (pin "2") (pinfunction "2_2") (pintype "passive"))
      (node (ref "R105") (pin "1") (pinfunction "1_1") (pintype "passive"))
      (node (ref "R109") (pin "1") (pinfunction "1_1") (pintype "passive"))
      (node (ref "R117") (pin "1") (pinfunction "1_1") (pintype "passive"))
      (node (ref "R185") (pin "1") (pinfunction "1_1") (pintype "passive"))
      (node (ref "R190") (pin "1") (pinfunction "1_1") (pintype "passive"))
      (node (ref "R195") (pin "1") (pinfunction "1_1") (pintype "passive"))
      (node (ref "R83") (pin "1") (pinfunction "1_1") (pintype "passive"))
      (node (ref "R97") (pin "1") (pinfunction "1_1") (pintype "passive"))
      (node (ref "U18") (pin "5") (pinfunction "V-_5") (pintype "power_in"))
      (node (ref "U21") (pin "5") (pinfunction "V-_5") (pintype "power_in"))
      (node (ref "U23") (pin "5") (pinfunction "V-_5") (pintype "power_in"))
      (node (ref "U38") (pin "2") (pinfunction "-V_2") (pintype "power_in"))
      (node (ref "U40") (pin "2") (pinfunction "-V_2") (pintype "power_in"))
      (node (ref "U41") (pin "2") (pinfunction "-V_2") (pintype "power_in"))
    )
    (net (code "9") (name "IU") (class "Default")
      (node (ref "R117") (pin "2") (pinfunction "2_2") (pintype "passive"))
      (node (ref "R120") (pin "1") (pinfunction "1_1") (pintype "passive"))
    )
    (net (code "10") (name "IU_MEAS") (class "Default")
      (node (ref "C21") (pin "1") (pinfunction "1_1") (pintype "passive"))
      (node (ref "R189") (pin "2") (pinfunction "2_2") (pintype "passive"))
    )
    (net (code "11") (name "IV") (class "Default")
      (node (ref "R109") (pin "2") (pinfunction "2_2") (pintype "passive"))
      (node (ref "R114") (pin "1") (pinfunction "1_1") (pintype "passive"))
    )
    (net (code "12") (name "IV_MEAS") (class "Default")
      (node (ref "C23") (pin "1") (pinfunction "1_1") (pintype "passive"))
      (node (ref "R192") (pin "2") (pinfunction "2_2") (pintype "passive"))
    )
    (net (code "13") (name "IW") (class "Default")
      (node (ref "R105") (pin "2") (pinfunction "2_2") (pintype "passive"))
      (node (ref "R106") (pin "1") (pinfunction "1_1") (pintype "passive"))
    )
    (net (code "14") (name "IW_MEAS") (class "Default")
      (node (ref "C25") (pin "1") (pinfunction "1_1") (pintype "passive"))
      (node (ref "R64") (pin "2") (pinfunction "2_2") (pintype "passive"))
    )
    (net (code "15") (name "Net-(U18A--IN_A)") (class "Default")
      (node (ref "C45") (pin "1") (pinfunction "1_1") (pintype "passive"))
      (node (ref "R87") (pin "2") (pinfunction "2_2") (pintype "passive"))
      (node (ref "U18") (pin "2") (pinfunction "-IN_A_2") (pintype "tri_state"))
      (node (ref "U18") (pin "3") (pinfunction "+IN_B_3") (pintype "tri_state"))
    )
    (net (code "16") (name "Net-(U18A-OUT_A)") (class "Default")
      (node (ref "R84") (pin "1") (pinfunction "1_1") (pintype "passive"))
      (node (ref "U18") (pin "7") (pinfunction "OUT_A_7") (pintype "passive"))
    )
    (net (code "17") (name "Net-(U18B-OUT_B)") (class "Default")
      (node (ref "R85") (pin "1") (pinfunction "1_1") (pintype "passive"))
      (node (ref "U18") (pin "6") (pinfunction "OUT_B_6") (pintype "passive"))
    )
    (net (code "18") (name "Net-(U21A--IN_A)") (class "Default")
      (node (ref "C69") (pin "1") (pinfunction "1_1") (pintype "passive"))
      (node (ref "R103") (pin "2") (pinfunction "2_2") (pintype "passive"))
      (node (ref "U21") (pin "2") (pinfunction "-IN_A_2") (pintype "tri_state"))
      (node (ref "U21") (pin "3") (pinfunction "+IN_B_3") (pintype "tri_state"))
    )
    (net (code "19") (name "Net-(U21A-OUT_A)") (class "Default")
      (node (ref "R86") (pin "1") (pinfunction "1_1") (pintype "passive"))
      (node (ref "U21") (pin "7") (pinfunction "OUT_A_7") (pintype "passive"))
    )
    (net (code "20") (name "Net-(U21B-OUT_B)") (class "Default")
      (node (ref "R90") (pin "1") (pinfunction "1_1") (pintype "passive"))
      (node (ref "U21") (pin "6") (pinfunction "OUT_B_6") (pintype "passive"))
    )
    (net (code "21") (name "Net-(U23A--IN_A)") (class "Default")
      (node (ref "C70") (pin "1") (pinfunction "1_1") (pintype "passive"))
      (node (ref "R104") (pin "2") (pinfunction "2_2") (pintype "passive"))
      (node (ref "U23") (pin "2") (pinfunction "-IN_A_2") (pintype "tri_state"))
      (node (ref "U23") (pin "3") (pinfunction "+IN_B_3") (pintype "tri_state"))
    )
    (net (code "22") (name "Net-(U23A-OUT_A)") (class "Default")
      (node (ref "R96") (pin "1") (pinfunction "1_1") (pintype "passive"))
      (node (ref "U23") (pin "7") (pinfunction "OUT_A_7") (pintype "passive"))
    )
    (net (code "23") (name "Net-(U23B-OUT_B)") (class "Default")
      (node (ref "R100") (pin "1") (pinfunction "1_1") (pintype "passive"))
      (node (ref "U23") (pin "6") (pinfunction "OUT_B_6") (pintype "passive"))
    )
    (net (code "24") (name "Net-(U38-+IN)") (class "Default")
      (node (ref "C129") (pin "1") (pinfunction "1_1") (pintype "passive"))
      (node (ref "R184") (pin "2") (pinfunction "2_2") (pintype "passive"))
      (node (ref "U38") (pin "3") (pinfunction "+IN_3") (pintype "input"))
    )
    (net (code "25") (name "Net-(U38--IN)") (class "Default")
      (node (ref "C130") (pin "1") (pinfunction "1_1") (pintype "passive"))
      (node (ref "R186") (pin "1") (pinfunction "1_1") (pintype "passive"))
      (node (ref "U38") (pin "4") (pinfunction "-IN_4") (pintype "input"))
    )
    (net (code "26") (name "Net-(U38-OUT)") (class "Default")
      (node (ref "C130") (pin "2") (pinfunction "2_2") (pintype "passive"))
      (node (ref "R186") (pin "2") (pinfunction "2_2") (pintype "passive"))
      (node (ref "R189") (pin "1") (pinfunction "1_1") (pintype "passive"))
      (node (ref "U38") (pin "1") (pinfunction "OUT_1") (pintype "output"))
    )
    (net (code "27") (name "Net-(U40-+IN)") (class "Default")
      (node (ref "C135") (pin "1") (pinfunction "1_1") (pintype "passive"))
      (node (ref "R188") (pin "2") (pinfunction "2_2") (pintype "passive"))
      (node (ref "U40") (pin "3") (pinfunction "+IN_3") (pintype "input"))
    )
    (net (code "28") (name "Net-(U40--IN)") (class "Default")
      (node (ref "C136") (pin "1") (pinfunction "1_1") (pintype "passive"))
      (node (ref "R191") (pin "1") (pinfunction "1_1") (pintype "passive"))
      (node (ref "U40") (pin "4") (pinfunction "-IN_4") (pintype "input"))
    )
    (net (code "29") (name "Net-(U40-OUT)") (class "Default")
      (node (ref "C136") (pin "2") (pinfunction "2_2") (pintype "passive"))
      (node (ref "R191") (pin "2") (pinfunction "2_2") (pintype "passive"))
      (node (ref "R192") (pin "1") (pinfunction "1_1") (pintype "passive"))
      (node (ref "U40") (pin "1") (pinfunction "OUT_1") (pintype "output"))
    )
    (net (code "30") (name "Net-(U41-+IN)") (class "Default")
      (node (ref "C141") (pin "1") (pinfunction "1_1") (pintype "passive"))
      (node (ref "R194") (pin "2") (pinfunction "2_2") (pintype "passive"))
      (node (ref "U41") (pin "3") (pinfunction "+IN_3") (pintype "input"))
    )
    (net (code "31") (name "Net-(U41--IN)") (class "Default")
      (node (ref "C142") (pin "1") (pinfunction "1_1") (pintype "passive"))
      (node (ref "R196") (pin "1") (pinfunction "1_1") (pintype "passive"))
      (node (ref "U41") (pin "4") (pinfunction "-IN_4") (pintype "input"))
    )
    (net (code "32") (name "Net-(U41-OUT)") (class "Default")
      (node (ref "C142") (pin "2") (pinfunction "2_2") (pintype "passive"))
      (node (ref "R196") (pin "2") (pinfunction "2_2") (pintype "passive"))
      (node (ref "R64") (pin "1") (pinfunction "1_1") (pintype "passive"))
      (node (ref "U41") (pin "1") (pinfunction "OUT_1") (pintype "output"))
    )
    (net (code "33") (name "U_HI_OC") (class "Default")
      (node (ref "C145") (pin "1") (pinfunction "1_1") (pintype "passive"))
      (node (ref "R84") (pin "2") (pinfunction "2_2") (pintype "passive"))
    )
    (net (code "34") (name "U_LO_OC") (class "Default")
      (node (ref "C146") (pin "1") (pinfunction "1_1") (pintype "passive"))
      (node (ref "R85") (pin "2") (pinfunction "2_2") (pintype "passive"))
    )
    (net (code "35") (name "V_HI_OC") (class "Default")
      (node (ref "C148") (pin "1") (pinfunction "1_1") (pintype "passive"))
      (node (ref "R86") (pin "2") (pinfunction "2_2") (pintype "passive"))
    )
    (net (code "36") (name "V_LO_OC") (class "Default")
      (node (ref "C149") (pin "1") (pinfunction "1_1") (pintype "passive"))
      (node (ref "R90") (pin "2") (pinfunction "2_2") (pintype "passive"))
    )
    (net (code "37") (name "W_HI_OC") (class "Default")
      (node (ref "C152") (pin "1") (pinfunction "1_1") (pintype "passive"))
      (node (ref "R96") (pin "2") (pinfunction "2_2") (pintype "passive"))
    )
    (net (code "38") (name "W_LO_OC") (class "Default")
      (node (ref "C154") (pin "1") (pinfunction "1_1") (pintype "passive"))
      (node (ref "R100") (pin "2") (pinfunction "2_2") (pintype "passive"))
    )
  )
)
